# DistanceSensorFront.net
KiCad netlist of a schematic drawn in Altium Designer
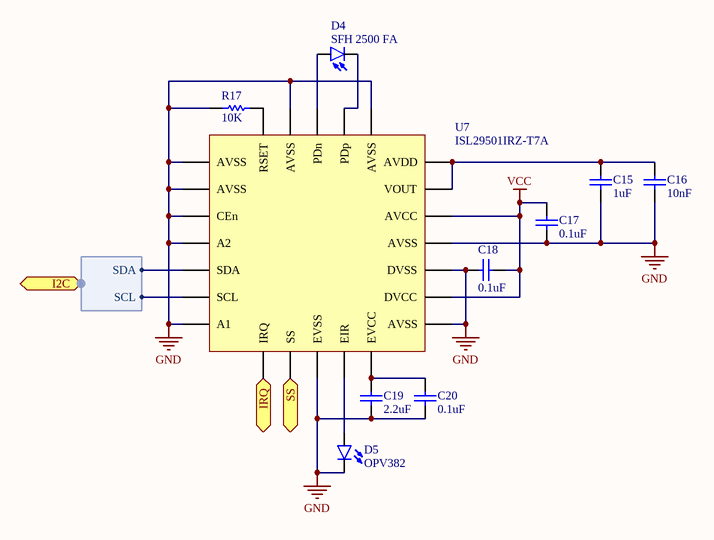
[diagram p0: DistanceSensorFront.SchDoc]

(export (version "E")
  (design (tool "Eeschema 10.0.6"))
  (components
    (comp (ref "C15")
      (value "1uF")
      (footprint "C0402[1005X55]")
      (description "1uF 6.3V 10% 0402 (1005 Metric)")
      (fields (field (name "PARTNUMBER") "GRM155R70J105KA12D") (field (name "MANUFACTURER") "Murata"))
      (libsource (lib "Capacitors") (part "CAP_1uF_6.3V_0402_10%"))
    )
    (comp (ref "C16")
      (value "10nF")
      (footprint "C0402[1005X55]")
      (description "10nF 50V 10% 0402 (1005 Metric)")
      (fields (field (name "PARTNUMBER") "GCM155R71H103KA55D") (field (name "MANUFACTURER") "Murata"))
      (libsource (lib "Capacitors") (part "CAP_10nF_50V_0402_10%"))
    )
    (comp (ref "C17")
      (value "0.1uF")
      (footprint "C0402[1005X55]")
      (description "0.1uF 6.3V 10% 0402 (1005 Metric)")
      (fields (field (name "PARTNUMBER") "GRM155R70J104KA01D") (field (name "MANUFACTURER") "Murata"))
      (libsource (lib "Capacitors") (part "CAP_0.1uF_6.3V_0402_10%"))
    )
    (comp (ref "C18")
      (value "0.1uF")
      (footprint "C0402[1005X55]")
      (description "0.1uF 6.3V 10% 0402 (1005 Metric)")
      (fields (field (name "PARTNUMBER") "GRM155R70J104KA01D") (field (name "MANUFACTURER") "Murata"))
      (libsource (lib "Capacitors") (part "CAP_0.1uF_6.3V_0402_10%"))
    )
    (comp (ref "C19")
      (value "2.2uF")
      (footprint "C0402[1005X55]")
      (description "2.2uF 6.3V 20% 0402 (1005 Metric)")
      (fields (field (name "PARTNUMBER") "GRM155R60J225ME15D") (field (name "MANUFACTURER") "Murata"))
      (libsource (lib "Capacitors") (part "CAP_2.2uF_6.3V_0402_20%"))
    )
    (comp (ref "C20")
      (value "0.1uF")
      (footprint "C0402[1005X55]")
      (description "0.1uF 6.3V 10% 0402 (1005 Metric)")
      (fields (field (name "PARTNUMBER") "GRM155R70J104KA01D") (field (name "MANUFACTURER") "Murata"))
      (libsource (lib "Capacitors") (part "CAP_0.1uF_6.3V_0402_10%"))
    )
    (comp (ref "D4")
      (value "SFH 2500 FA")
      (footprint "SFH 2500 FA")
      (fields (field (name "MANUFACTURER") "Osram"))
      (libsource (lib "Components") (part "SFH 2500 FA"))
    )
    (comp (ref "D5")
      (value "OPV382")
      (footprint "OPV382")
      (fields (field (name "MANUFACTURER") "OPTEK Technology"))
      (libsource (lib "Components") (part "OPV382"))
    )
    (comp (ref "R17")
      (value "10K")
      (footprint "R0402[1005]")
      (description "10K 0.063W 1% 0402 (1005 Metric)")
      (fields (field (name "MANUFACTURER") "KOA Speer") (field (name "PARTNUMBER") "RK73H1ETTP1002F"))
      (libsource (lib "Resistors") (part "RES_10K_0402_1%"))
    )
    (comp (ref "U7")
      (value "ISL29501IRZ-T7A")
      (footprint "QFN-24")
      (description "IC TOF SIGNAL PROCESSOR 24QFN")
      (fields (field (name "MANUFACTURER") "Intersil"))
      (libsource (lib "ICs") (part "ISL29501IRZ-T7A"))
    )
  )
  (nets
    (net (code "2") (name "/IRQ") (class "Default")
      (node (ref "U7") (pin "8") (pinfunction "IRQ_8") (pintype "passive"))
    )
    (net (code "3") (name "/SCL") (class "Default")
      (node (ref "U7") (pin "6") (pinfunction "SCL_6") (pintype "passive"))
    )
    (net (code "4") (name "/SDA") (class "Default")
      (node (ref "U7") (pin "5") (pinfunction "SDA_5") (pintype "passive"))
    )
    (net (code "5") (name "/SS") (class "Default")
      (node (ref "U7") (pin "9") (pinfunction "SS_9") (pintype "passive"))
    )
    (net (code "7") (name "GND") (class "Default")
      (node (ref "C15") (pin "1") (pinfunction "1_1") (pintype "passive"))
      (node (ref "C16") (pin "1") (pinfunction "1_1") (pintype "passive"))
      (node (ref "C17") (pin "2") (pinfunction "2_2") (pintype "passive"))
      (node (ref "C18") (pin "2") (pinfunction "2_2") (pintype "passive"))
      (node (ref "C19") (pin "1") (pinfunction "1_1") (pintype "passive"))
      (node (ref "C20") (pin "1") (pinfunction "1_1") (pintype "passive"))
      (node (ref "D5") (pin "1") (pinfunction "C_1") (pintype "passive"))
      (node (ref "R17") (pin "1") (pinfunction "1_1") (pintype "passive"))
      (node (ref "U7") (pin "1") (pinfunction "AVSS_1") (pintype "passive"))
      (node (ref "U7") (pin "10") (pinfunction "EVSS_10") (pintype "passive"))
      (node (ref "U7") (pin "13") (pinfunction "AVSS_13") (pintype "passive"))
      (node (ref "U7") (pin "15") (pinfunction "DVSS_15") (pintype "passive"))
      (node (ref "U7") (pin "16") (pinfunction "AVSS_16") (pintype "passive"))
      (node (ref "U7") (pin "2") (pinfunction "AVSS_2") (pintype "passive"))
      (node (ref "U7") (pin "20") (pinfunction "AVSS_20") (pintype "passive"))
      (node (ref "U7") (pin "23") (pinfunction "AVSS_23") (pintype "passive"))
      (node (ref "U7") (pin "3") (pinfunction "CEn_3") (pintype "passive"))
      (node (ref "U7") (pin "4") (pinfunction "A2_4") (pintype "power_in"))
      (node (ref "U7") (pin "7") (pinfunction "A1_7") (pintype "passive"))
    )
    (net (code "8") (name "Net-(D4-A)") (class "Default")
      (node (ref "D4") (pin "2") (pinfunction "A_2") (pintype "passive"))
      (node (ref "U7") (pin "22") (pinfunction "PDn_22") (pintype "passive"))
    )
    (net (code "9") (name "Net-(D4-C)") (class "Default")
      (node (ref "D4") (pin "1") (pinfunction "C_1") (pintype "passive"))
      (node (ref "U7") (pin "21") (pinfunction "PDp_21") (pintype "passive"))
    )
    (net (code "10") (name "Net-(D5-A)") (class "Default")
      (node (ref "D5") (pin "2") (pinfunction "A_2") (pintype "passive"))
      (node (ref "U7") (pin "11") (pinfunction "EIR_11") (pintype "passive"))
    )
    (net (code "11") (name "Net-(U7-AVDD)") (class "Default")
      (node (ref "C15") (pin "2") (pinfunction "2_2") (pintype "passive"))
      (node (ref "C16") (pin "2") (pinfunction "2_2") (pintype "passive"))
      (node (ref "U7") (pin "18") (pinfunction "VOUT_18") (pintype "passive"))
      (node (ref "U7") (pin "19") (pinfunction "AVDD_19") (pintype "passive"))
    )
    (net (code "12") (name "Net-(U7-EVCC)") (class "Default")
      (node (ref "C19") (pin "2") (pinfunction "2_2") (pintype "passive"))
      (node (ref "C20") (pin "2") (pinfunction "2_2") (pintype "passive"))
      (node (ref "U7") (pin "12") (pinfunction "EVCC_12") (pintype "passive"))
    )
    (net (code "13") (name "Net-(U7-RSET)") (class "Default")
      (node (ref "R17") (pin "2") (pinfunction "2_2") (pintype "passive"))
      (node (ref "U7") (pin "24") (pinfunction "RSET_24") (pintype "passive"))
    )
    (net (code "14") (name "VCC") (class "Default")
      (node (ref "C17") (pin "1") (pinfunction "1_1") (pintype "passive"))
      (node (ref "C18") (pin "1") (pinfunction "1_1") (pintype "passive"))
      (node (ref "U7") (pin "14") (pinfunction "DVCC_14") (pintype "passive"))
      (node (ref "U7") (pin "17") (pinfunction "AVCC_17") (pintype "passive"))
    )
  )
)
